# sdmapper.net
KiCad netlist of a schematic drawn in EAGLE
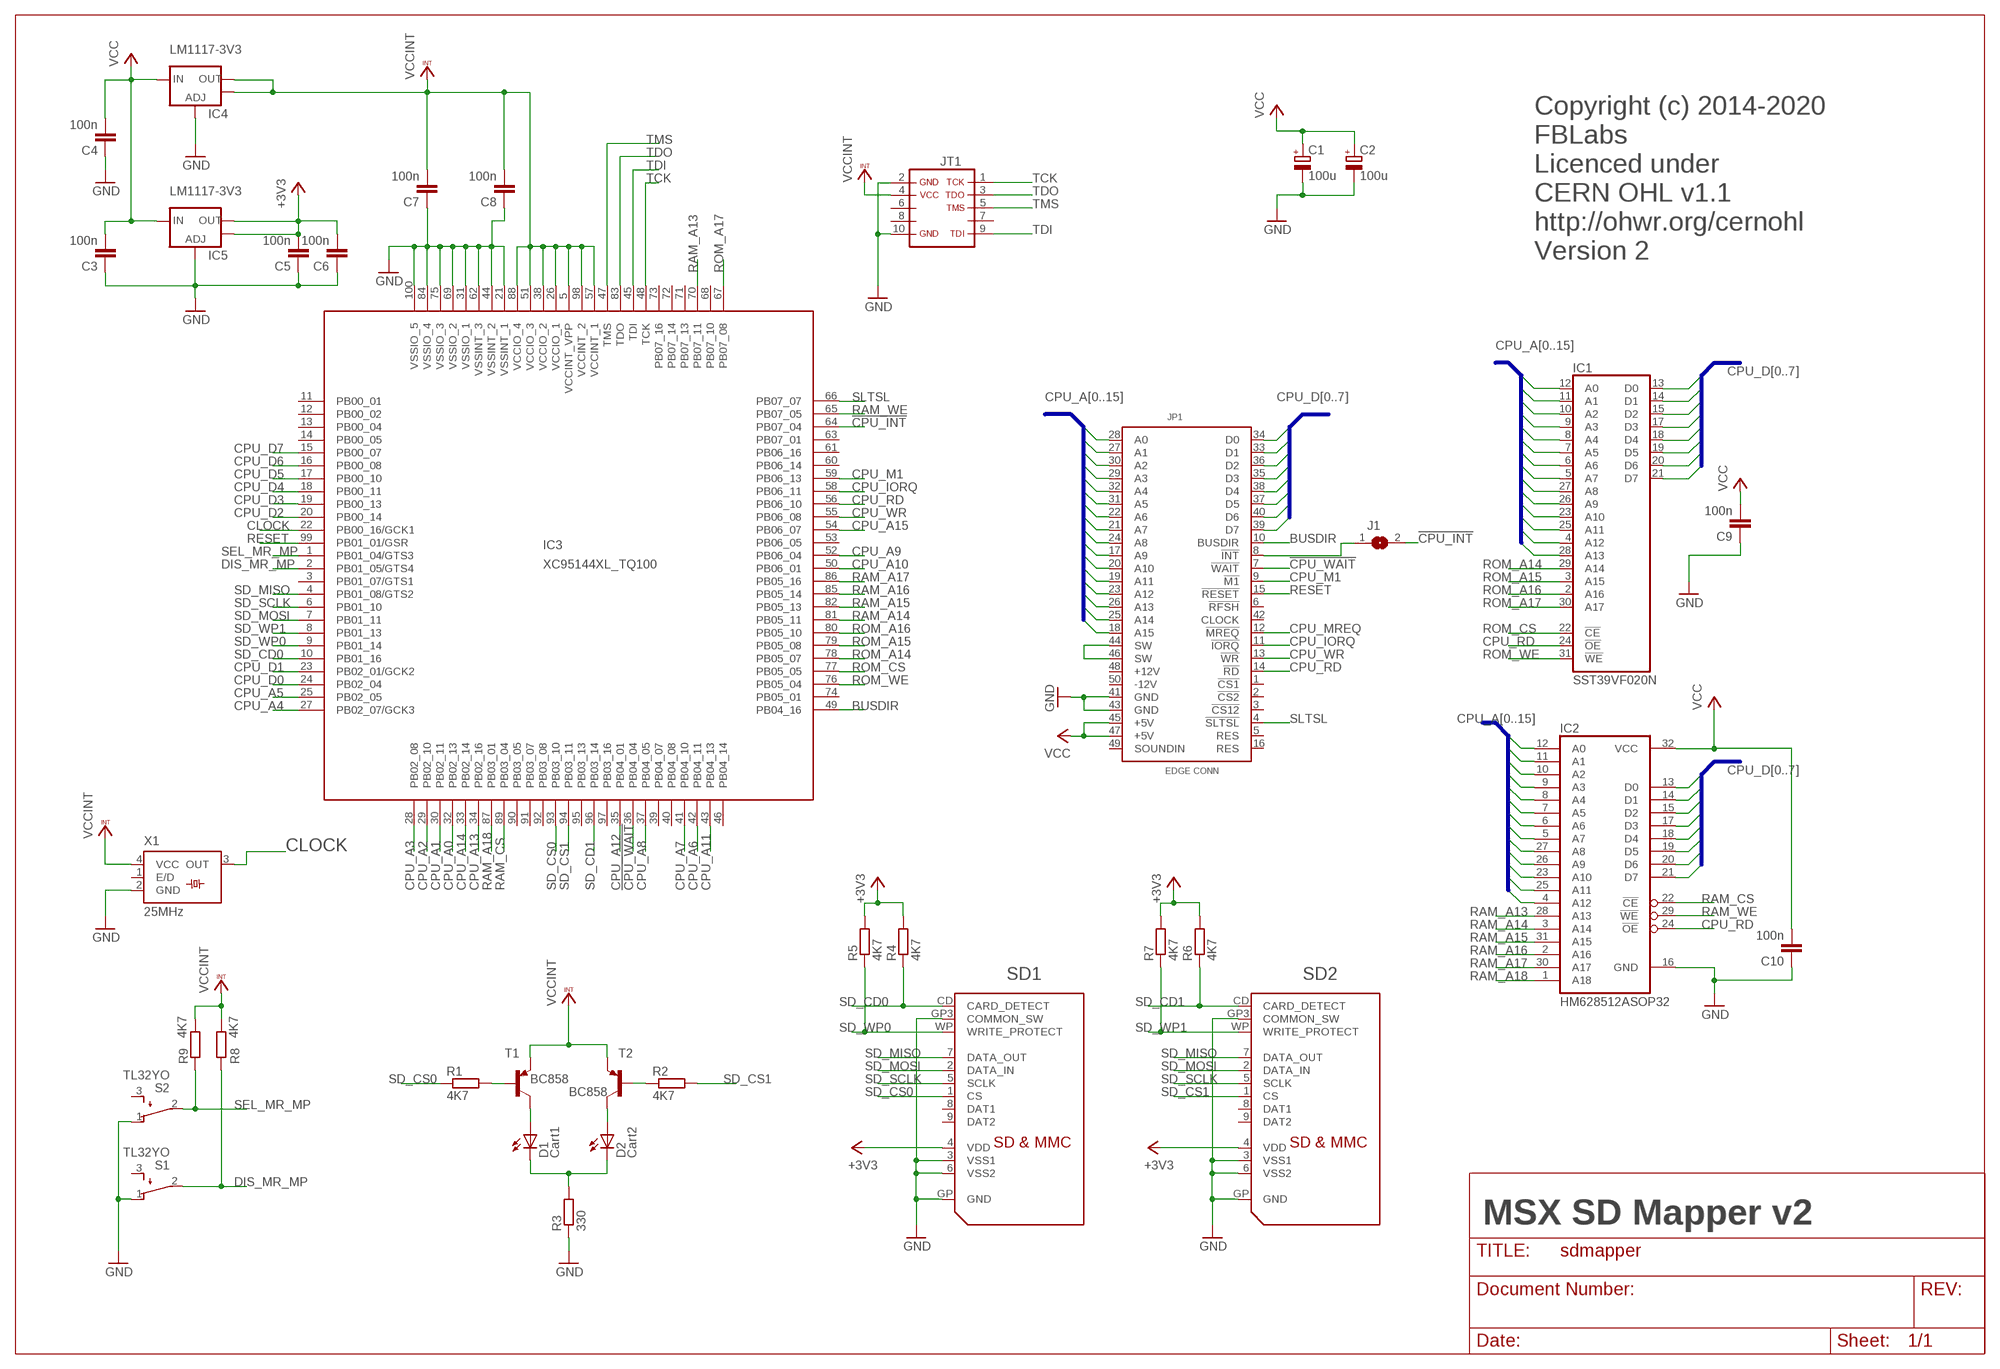
[diagram p0: schematic, sheet 1]

(export (version "E")
  (design (tool "Eeschema 10.0.6"))
  (components
    (comp (ref "C1")
      (value "100u")
      (footprint "eagle-import:E3,5-6")
      (libsource (lib "eagle-import") (part "CPOL-EUE3,5-6"))
    )
    (comp (ref "C2")
      (value "100u")
      (footprint "eagle-import:PANASONIC_C")
      (libsource (lib "eagle-import") (part "CPOL-EUC"))
    )
    (comp (ref "C3")
      (value "100n")
      (footprint "eagle-import:C0805")
      (libsource (lib "eagle-import") (part "C-EUC0805"))
    )
    (comp (ref "C4")
      (value "100n")
      (footprint "eagle-import:C0805")
      (libsource (lib "eagle-import") (part "C-EUC0805"))
    )
    (comp (ref "C5")
      (value "100n")
      (footprint "eagle-import:C0805")
      (libsource (lib "eagle-import") (part "C-EUC0805"))
    )
    (comp (ref "C6")
      (value "100n")
      (footprint "eagle-import:C0805")
      (libsource (lib "eagle-import") (part "C-EUC0805"))
    )
    (comp (ref "C7")
      (value "100n")
      (footprint "eagle-import:C0805")
      (libsource (lib "eagle-import") (part "C-EUC0805"))
    )
    (comp (ref "C8")
      (value "100n")
      (footprint "eagle-import:C0805")
      (libsource (lib "eagle-import") (part "C-EUC0805"))
    )
    (comp (ref "C9")
      (value "100n")
      (footprint "eagle-import:C0805")
      (libsource (lib "eagle-import") (part "C-EUC0805"))
    )
    (comp (ref "C10")
      (value "100n")
      (footprint "eagle-import:C0805")
      (libsource (lib "eagle-import") (part "C-EUC0805"))
    )
    (comp (ref "D1")
      (value "Cart1")
      (footprint "eagle-import:LED3MM")
      (libsource (lib "eagle-import") (part "LED3MM"))
    )
    (comp (ref "D2")
      (value "Cart2")
      (footprint "eagle-import:LED3MM")
      (libsource (lib "eagle-import") (part "LED3MM"))
    )
    (comp (ref "IC1")
      (value "SST39VF020N")
      (footprint "eagle-import:PLCC32R")
      (libsource (lib "eagle-import") (part "SST39VF020N"))
    )
    (comp (ref "IC2")
      (value "HM628512ASOP32")
      (footprint "eagle-import:SOP32")
      (libsource (lib "eagle-import") (part "HM628512ASOP32"))
    )
    (comp (ref "IC3")
      (value "XC95144XL_TQ100")
      (footprint "eagle-import:XC-TQ100")
      (libsource (lib "eagle-import") (part "XC95144XL_TQ100"))
    )
    (comp (ref "IC4")
      (value "LM1117-3V3")
      (footprint "eagle-import:SOT223")
      (libsource (lib "eagle-import") (part "V_REG_LM1117SOT223"))
    )
    (comp (ref "IC5")
      (value "LM1117-3V3")
      (footprint "eagle-import:SOT223")
      (libsource (lib "eagle-import") (part "V_REG_LM1117SOT223"))
    )
    (comp (ref "J1")
      (value "SJ4")
      (footprint "eagle-import:SJ20")
      (libsource (lib "eagle-import") (part "SJ4"))
    )
    (comp (ref "JP1")
      (value "MSXCART1")
      (footprint "eagle-import:MSXCART")
      (libsource (lib "eagle-import") (part "MSXCART1"))
    )
    (comp (ref "JT1")
      (value "JTAG1B")
      (footprint "eagle-import:SMD5X2")
      (libsource (lib "eagle-import") (part "JTAG1B"))
    )
    (comp (ref "R1")
      (value "4K7")
      (footprint "eagle-import:R0805")
      (libsource (lib "eagle-import") (part "R-EU_R0805"))
    )
    (comp (ref "R2")
      (value "4K7")
      (footprint "eagle-import:R0805")
      (libsource (lib "eagle-import") (part "R-EU_R0805"))
    )
    (comp (ref "R3")
      (value "330")
      (footprint "eagle-import:R0805")
      (libsource (lib "eagle-import") (part "R-EU_R0805"))
    )
    (comp (ref "R4")
      (value "4K7")
      (footprint "eagle-import:R0805")
      (libsource (lib "eagle-import") (part "R-EU_R0805"))
    )
    (comp (ref "R5")
      (value "4K7")
      (footprint "eagle-import:R0805")
      (libsource (lib "eagle-import") (part "R-EU_R0805"))
    )
    (comp (ref "R6")
      (value "4K7")
      (footprint "eagle-import:R0805")
      (libsource (lib "eagle-import") (part "R-EU_R0805"))
    )
    (comp (ref "R7")
      (value "4K7")
      (footprint "eagle-import:R0805")
      (libsource (lib "eagle-import") (part "R-EU_R0805"))
    )
    (comp (ref "R8")
      (value "4K7")
      (footprint "eagle-import:R0805")
      (libsource (lib "eagle-import") (part "R-EU_R0805"))
    )
    (comp (ref "R9")
      (value "4K7")
      (footprint "eagle-import:R0805")
      (libsource (lib "eagle-import") (part "R-EU_R0805"))
    )
    (comp (ref "S1")
      (value "TL32YO")
      (footprint "eagle-import:TL3XYO")
      (libsource (lib "eagle-import") (part "TL32YO"))
    )
    (comp (ref "S2")
      (value "TL32YO")
      (footprint "eagle-import:TL3XYO")
      (libsource (lib "eagle-import") (part "TL32YO"))
    )
    (comp (ref "SD1")
      (value "SDMMC06132")
      (footprint "eagle-import:06132")
      (libsource (lib "eagle-import") (part "SDMMC06132"))
    )
    (comp (ref "SD2")
      (value "SDMMC06132")
      (footprint "eagle-import:06132")
      (libsource (lib "eagle-import") (part "SDMMC06132"))
    )
    (comp (ref "T1")
      (value "BC858")
      (footprint "eagle-import:SOT23-BEC")
      (libsource (lib "eagle-import") (part "-PNP-SOT23-BECBC858A"))
    )
    (comp (ref "T2")
      (value "BC858")
      (footprint "eagle-import:SOT23-BEC")
      (libsource (lib "eagle-import") (part "-PNP-SOT23-BECBC858A"))
    )
    (comp (ref "X1")
      (value "25MHz")
      (footprint "eagle-import:SM77H")
      (libsource (lib "eagle-import") (part "SM77H"))
    )
  )
  (nets
    (net (code "1") (name "+3V3") (class "Default")
      (node (ref "C5") (pin "2") (pinfunction "2_2") (pintype "passive"))
      (node (ref "C6") (pin "2") (pinfunction "2_2") (pintype "passive"))
      (node (ref "IC5") (pin "2") (pinfunction "OUT_2") (pintype "output"))
      (node (ref "IC5") (pin "4") (pinfunction "OUT_4") (pintype "output"))
      (node (ref "R4") (pin "2") (pinfunction "2_2") (pintype "passive"))
      (node (ref "R5") (pin "2") (pinfunction "2_2") (pintype "passive"))
      (node (ref "R6") (pin "2") (pinfunction "2_2") (pintype "passive"))
      (node (ref "R7") (pin "2") (pinfunction "2_2") (pintype "passive"))
      (node (ref "SD1") (pin "4") (pinfunction "VDD_4") (pintype "power_in"))
      (node (ref "SD2") (pin "4") (pinfunction "VDD_4") (pintype "power_in"))
    )
    (net (code "2") (name "/+12V") (class "Default")
      (node (ref "JP1") (pin "48") (pinfunction "+12V_48") (pintype "power_in"))
    )
    (net (code "3") (name "/-12V") (class "Default")
      (node (ref "JP1") (pin "50") (pinfunction "-12V_50") (pintype "power_in"))
    )
    (net (code "4") (name "/BUSDIR") (class "Default")
      (node (ref "IC3") (pin "49") (pinfunction "PB04_16_49") (pintype "bidirectional"))
      (node (ref "JP1") (pin "10") (pinfunction "BUSDIR_10") (pintype "input"))
    )
    (net (code "5") (name "/CLOCK") (class "Default")
      (node (ref "IC3") (pin "22") (pinfunction "PB00_16/GCK1_22") (pintype "bidirectional"))
      (node (ref "X1") (pin "3") (pinfunction "OUT_3") (pintype "output"))
    )
    (net (code "6") (name "/CPU_A0") (class "Default")
      (node (ref "IC1") (pin "12") (pinfunction "A0_12") (pintype "input"))
      (node (ref "IC2") (pin "12") (pinfunction "A0_12") (pintype "input"))
      (node (ref "IC3") (pin "32") (pinfunction "PB02_13_32") (pintype "bidirectional"))
      (node (ref "JP1") (pin "28") (pinfunction "A0_28") (pintype "output"))
    )
    (net (code "7") (name "/CPU_A1") (class "Default")
      (node (ref "IC1") (pin "11") (pinfunction "A1_11") (pintype "input"))
      (node (ref "IC2") (pin "11") (pinfunction "A1_11") (pintype "input"))
      (node (ref "IC3") (pin "30") (pinfunction "PB02_11_30") (pintype "bidirectional"))
      (node (ref "JP1") (pin "27") (pinfunction "A1_27") (pintype "output"))
    )
    (net (code "8") (name "/CPU_A2") (class "Default")
      (node (ref "IC1") (pin "10") (pinfunction "A2_10") (pintype "input"))
      (node (ref "IC2") (pin "10") (pinfunction "A2_10") (pintype "input"))
      (node (ref "IC3") (pin "29") (pinfunction "PB02_10_29") (pintype "bidirectional"))
      (node (ref "JP1") (pin "30") (pinfunction "A2_30") (pintype "output"))
    )
    (net (code "9") (name "/CPU_A3") (class "Default")
      (node (ref "IC1") (pin "9") (pinfunction "A3_9") (pintype "input"))
      (node (ref "IC2") (pin "9") (pinfunction "A3_9") (pintype "input"))
      (node (ref "IC3") (pin "28") (pinfunction "PB02_08_28") (pintype "bidirectional"))
      (node (ref "JP1") (pin "29") (pinfunction "A3_29") (pintype "output"))
    )
    (net (code "10") (name "/CPU_A4") (class "Default")
      (node (ref "IC1") (pin "8") (pinfunction "A4_8") (pintype "input"))
      (node (ref "IC2") (pin "8") (pinfunction "A4_8") (pintype "input"))
      (node (ref "IC3") (pin "27") (pinfunction "PB02_07/GCK3_27") (pintype "bidirectional"))
      (node (ref "JP1") (pin "32") (pinfunction "A4_32") (pintype "output"))
    )
    (net (code "11") (name "/CPU_A5") (class "Default")
      (node (ref "IC1") (pin "7") (pinfunction "A5_7") (pintype "input"))
      (node (ref "IC2") (pin "7") (pinfunction "A5_7") (pintype "input"))
      (node (ref "IC3") (pin "25") (pinfunction "PB02_05_25") (pintype "bidirectional"))
      (node (ref "JP1") (pin "31") (pinfunction "A5_31") (pintype "output"))
    )
    (net (code "12") (name "/CPU_A6") (class "Default")
      (node (ref "IC1") (pin "6") (pinfunction "A6_6") (pintype "input"))
      (node (ref "IC2") (pin "6") (pinfunction "A6_6") (pintype "input"))
      (node (ref "IC3") (pin "42") (pinfunction "PB04_11_42") (pintype "bidirectional"))
      (node (ref "JP1") (pin "22") (pinfunction "A6_22") (pintype "output"))
    )
    (net (code "13") (name "/CPU_A7") (class "Default")
      (node (ref "IC1") (pin "5") (pinfunction "A7_5") (pintype "input"))
      (node (ref "IC2") (pin "5") (pinfunction "A7_5") (pintype "input"))
      (node (ref "IC3") (pin "41") (pinfunction "PB04_10_41") (pintype "bidirectional"))
      (node (ref "JP1") (pin "21") (pinfunction "A7_21") (pintype "output"))
    )
    (net (code "14") (name "/CPU_A8") (class "Default")
      (node (ref "IC1") (pin "27") (pinfunction "A8_27") (pintype "input"))
      (node (ref "IC2") (pin "27") (pinfunction "A8_27") (pintype "input"))
      (node (ref "IC3") (pin "37") (pinfunction "PB04_05_37") (pintype "bidirectional"))
      (node (ref "JP1") (pin "24") (pinfunction "A8_24") (pintype "output"))
    )
    (net (code "15") (name "/CPU_A9") (class "Default")
      (node (ref "IC1") (pin "26") (pinfunction "A9_26") (pintype "input"))
      (node (ref "IC2") (pin "26") (pinfunction "A9_26") (pintype "input"))
      (node (ref "IC3") (pin "52") (pinfunction "PB06_04_52") (pintype "bidirectional"))
      (node (ref "JP1") (pin "17") (pinfunction "A9_17") (pintype "output"))
    )
    (net (code "16") (name "/CPU_A10") (class "Default")
      (node (ref "IC1") (pin "23") (pinfunction "A10_23") (pintype "input"))
      (node (ref "IC2") (pin "23") (pinfunction "A10_23") (pintype "input"))
      (node (ref "IC3") (pin "50") (pinfunction "PB06_01_50") (pintype "bidirectional"))
      (node (ref "JP1") (pin "20") (pinfunction "A10_20") (pintype "output"))
    )
    (net (code "17") (name "/CPU_A11") (class "Default")
      (node (ref "IC1") (pin "25") (pinfunction "A11_25") (pintype "input"))
      (node (ref "IC2") (pin "25") (pinfunction "A11_25") (pintype "input"))
      (node (ref "IC3") (pin "43") (pinfunction "PB04_13_43") (pintype "bidirectional"))
      (node (ref "JP1") (pin "19") (pinfunction "A11_19") (pintype "output"))
    )
    (net (code "18") (name "/CPU_A12") (class "Default")
      (node (ref "IC1") (pin "4") (pinfunction "A12_4") (pintype "input"))
      (node (ref "IC2") (pin "4") (pinfunction "A12_4") (pintype "input"))
      (node (ref "IC3") (pin "35") (pinfunction "PB04_01_35") (pintype "bidirectional"))
      (node (ref "JP1") (pin "23") (pinfunction "A12_23") (pintype "output"))
    )
    (net (code "19") (name "/CPU_A13") (class "Default")
      (node (ref "IC1") (pin "28") (pinfunction "A13_28") (pintype "input"))
      (node (ref "IC3") (pin "34") (pinfunction "PB02_16_34") (pintype "bidirectional"))
      (node (ref "JP1") (pin "26") (pinfunction "A13_26") (pintype "output"))
    )
    (net (code "20") (name "/CPU_A14") (class "Default")
      (node (ref "IC3") (pin "33") (pinfunction "PB02_14_33") (pintype "bidirectional"))
      (node (ref "JP1") (pin "25") (pinfunction "A14_25") (pintype "output"))
    )
    (net (code "21") (name "/CPU_A15") (class "Default")
      (node (ref "IC3") (pin "54") (pinfunction "PB06_07_54") (pintype "bidirectional"))
      (node (ref "JP1") (pin "18") (pinfunction "A15_18") (pintype "output"))
    )
    (net (code "23") (name "/CPU_D0") (class "Default")
      (node (ref "IC1") (pin "13") (pinfunction "D0_13") (pintype "bidirectional"))
      (node (ref "IC2") (pin "13") (pinfunction "D0_13") (pintype "bidirectional"))
      (node (ref "IC3") (pin "24") (pinfunction "PB02_04_24") (pintype "bidirectional"))
      (node (ref "JP1") (pin "34") (pinfunction "D0_34") (pintype "bidirectional"))
    )
    (net (code "24") (name "/CPU_D1") (class "Default")
      (node (ref "IC1") (pin "14") (pinfunction "D1_14") (pintype "bidirectional"))
      (node (ref "IC2") (pin "14") (pinfunction "D1_14") (pintype "bidirectional"))
      (node (ref "IC3") (pin "23") (pinfunction "PB02_01/GCK2_23") (pintype "bidirectional"))
      (node (ref "JP1") (pin "33") (pinfunction "D1_33") (pintype "bidirectional"))
    )
    (net (code "25") (name "/CPU_D2") (class "Default")
      (node (ref "IC1") (pin "15") (pinfunction "D2_15") (pintype "bidirectional"))
      (node (ref "IC2") (pin "15") (pinfunction "D2_15") (pintype "bidirectional"))
      (node (ref "IC3") (pin "20") (pinfunction "PB00_14_20") (pintype "bidirectional"))
      (node (ref "JP1") (pin "36") (pinfunction "D2_36") (pintype "bidirectional"))
    )
    (net (code "26") (name "/CPU_D3") (class "Default")
      (node (ref "IC1") (pin "17") (pinfunction "D3_17") (pintype "bidirectional"))
      (node (ref "IC2") (pin "17") (pinfunction "D3_17") (pintype "bidirectional"))
      (node (ref "IC3") (pin "19") (pinfunction "PB00_13_19") (pintype "bidirectional"))
      (node (ref "JP1") (pin "35") (pinfunction "D3_35") (pintype "bidirectional"))
    )
    (net (code "27") (name "/CPU_D4") (class "Default")
      (node (ref "IC1") (pin "18") (pinfunction "D4_18") (pintype "bidirectional"))
      (node (ref "IC2") (pin "18") (pinfunction "D4_18") (pintype "bidirectional"))
      (node (ref "IC3") (pin "18") (pinfunction "PB00_11_18") (pintype "bidirectional"))
      (node (ref "JP1") (pin "38") (pinfunction "D4_38") (pintype "bidirectional"))
    )
    (net (code "28") (name "/CPU_D5") (class "Default")
      (node (ref "IC1") (pin "19") (pinfunction "D5_19") (pintype "bidirectional"))
      (node (ref "IC2") (pin "19") (pinfunction "D5_19") (pintype "bidirectional"))
      (node (ref "IC3") (pin "17") (pinfunction "PB00_10_17") (pintype "bidirectional"))
      (node (ref "JP1") (pin "37") (pinfunction "D5_37") (pintype "bidirectional"))
    )
    (net (code "29") (name "/CPU_D6") (class "Default")
      (node (ref "IC1") (pin "20") (pinfunction "D6_20") (pintype "bidirectional"))
      (node (ref "IC2") (pin "20") (pinfunction "D6_20") (pintype "bidirectional"))
      (node (ref "IC3") (pin "16") (pinfunction "PB00_08_16") (pintype "bidirectional"))
      (node (ref "JP1") (pin "40") (pinfunction "D6_40") (pintype "bidirectional"))
    )
    (net (code "30") (name "/CPU_D7") (class "Default")
      (node (ref "IC1") (pin "21") (pinfunction "D7_21") (pintype "bidirectional"))
      (node (ref "IC2") (pin "21") (pinfunction "D7_21") (pintype "bidirectional"))
      (node (ref "IC3") (pin "15") (pinfunction "PB00_07_15") (pintype "bidirectional"))
      (node (ref "JP1") (pin "39") (pinfunction "D7_39") (pintype "bidirectional"))
    )
    (net (code "32") (name "/CPU_IORQ") (class "Default")
      (node (ref "IC3") (pin "58") (pinfunction "PB06_11_58") (pintype "bidirectional"))
      (node (ref "JP1") (pin "11") (pinfunction "~{IORQ}_11") (pintype "output"))
    )
    (net (code "33") (name "/CPU_M1") (class "Default")
      (node (ref "IC3") (pin "59") (pinfunction "PB06_13_59") (pintype "bidirectional"))
      (node (ref "JP1") (pin "9") (pinfunction "~{M1}_9") (pintype "output"))
    )
    (net (code "34") (name "/CPU_MREQ") (class "Default")
      (node (ref "JP1") (pin "12") (pinfunction "~{MREQ}_12") (pintype "output"))
    )
    (net (code "35") (name "/CPU_RD") (class "Default")
      (node (ref "IC1") (pin "24") (pinfunction "~{OE}_24") (pintype "input"))
      (node (ref "IC2") (pin "24") (pinfunction "~{OE}_24") (pintype "input"))
      (node (ref "IC3") (pin "56") (pinfunction "PB06_10_56") (pintype "bidirectional"))
      (node (ref "JP1") (pin "14") (pinfunction "~{RD}_14") (pintype "output"))
    )
    (net (code "36") (name "/CPU_WR") (class "Default")
      (node (ref "IC3") (pin "55") (pinfunction "PB06_08_55") (pintype "bidirectional"))
      (node (ref "JP1") (pin "13") (pinfunction "~{WR}_13") (pintype "output"))
    )
    (net (code "37") (name "/DIS_MR_MP") (class "Default")
      (node (ref "IC3") (pin "2") (pinfunction "PB01_05/GTS4_2") (pintype "bidirectional"))
      (node (ref "R8") (pin "1") (pinfunction "1_1") (pintype "passive"))
      (node (ref "S1") (pin "2") (pinfunction "P_2") (pintype "passive"))
    )
    (net (code "38") (name "/RAM_A13") (class "Default")
      (node (ref "IC2") (pin "28") (pinfunction "A13_28") (pintype "input"))
      (node (ref "IC3") (pin "70") (pinfunction "PB07_11_70") (pintype "bidirectional"))
    )
    (net (code "39") (name "/RAM_A14") (class "Default")
      (node (ref "IC2") (pin "3") (pinfunction "A14_3") (pintype "input"))
      (node (ref "IC3") (pin "81") (pinfunction "PB05_11_81") (pintype "bidirectional"))
    )
    (net (code "40") (name "/RAM_A15") (class "Default")
      (node (ref "IC2") (pin "31") (pinfunction "A15_31") (pintype "input"))
      (node (ref "IC3") (pin "82") (pinfunction "PB05_13_82") (pintype "bidirectional"))
    )
    (net (code "41") (name "/RAM_A16") (class "Default")
      (node (ref "IC2") (pin "2") (pinfunction "A16_2") (pintype "input"))
      (node (ref "IC3") (pin "85") (pinfunction "PB05_14_85") (pintype "bidirectional"))
    )
    (net (code "42") (name "/RAM_A17") (class "Default")
      (node (ref "IC2") (pin "30") (pinfunction "A17_30") (pintype "input"))
      (node (ref "IC3") (pin "86") (pinfunction "PB05_16_86") (pintype "bidirectional"))
    )
    (net (code "43") (name "/RAM_A18") (class "Default")
      (node (ref "IC2") (pin "1") (pinfunction "A18_1") (pintype "input"))
      (node (ref "IC3") (pin "87") (pinfunction "PB03_01_87") (pintype "bidirectional"))
    )
    (net (code "44") (name "/RAM_CS") (class "Default")
      (node (ref "IC2") (pin "22") (pinfunction "~{CE}_22") (pintype "input"))
      (node (ref "IC3") (pin "89") (pinfunction "PB03_04_89") (pintype "bidirectional"))
    )
    (net (code "45") (name "/RAM_WE") (class "Default")
      (node (ref "IC2") (pin "29") (pinfunction "~{WE}_29") (pintype "input"))
      (node (ref "IC3") (pin "65") (pinfunction "PB07_05_65") (pintype "bidirectional"))
    )
    (net (code "46") (name "/RESET") (class "Default")
      (node (ref "IC3") (pin "99") (pinfunction "PB01_01/GSR_99") (pintype "bidirectional"))
      (node (ref "JP1") (pin "15") (pinfunction "~{RESET}_15") (pintype "output"))
    )
    (net (code "47") (name "/ROM_A14") (class "Default")
      (node (ref "IC1") (pin "29") (pinfunction "A14_29") (pintype "input"))
      (node (ref "IC3") (pin "78") (pinfunction "PB05_07_78") (pintype "bidirectional"))
    )
    (net (code "48") (name "/ROM_A15") (class "Default")
      (node (ref "IC1") (pin "3") (pinfunction "A15_3") (pintype "input"))
      (node (ref "IC3") (pin "79") (pinfunction "PB05_08_79") (pintype "bidirectional"))
    )
    (net (code "49") (name "/ROM_A16") (class "Default")
      (node (ref "IC1") (pin "2") (pinfunction "A16_2") (pintype "input"))
      (node (ref "IC3") (pin "80") (pinfunction "PB05_10_80") (pintype "bidirectional"))
    )
    (net (code "50") (name "/ROM_A17") (class "Default")
      (node (ref "IC1") (pin "30") (pinfunction "A17_30") (pintype "input"))
      (node (ref "IC3") (pin "67") (pinfunction "PB07_08_67") (pintype "bidirectional"))
    )
    (net (code "51") (name "/ROM_CS") (class "Default")
      (node (ref "IC1") (pin "22") (pinfunction "~{CE}_22") (pintype "input"))
      (node (ref "IC3") (pin "77") (pinfunction "PB05_05_77") (pintype "bidirectional"))
    )
    (net (code "52") (name "/ROM_WE") (class "Default")
      (node (ref "IC1") (pin "31") (pinfunction "~{WE}_31") (pintype "input"))
      (node (ref "IC3") (pin "76") (pinfunction "PB05_04_76") (pintype "bidirectional"))
    )
    (net (code "53") (name "/SD_CD0") (class "Default")
      (node (ref "IC3") (pin "10") (pinfunction "PB01_16_10") (pintype "bidirectional"))
      (node (ref "R4") (pin "1") (pinfunction "1_1") (pintype "passive"))
      (node (ref "SD1") (pin "CD") (pinfunction "CARD_DETECT_CD") (pintype "passive"))
    )
    (net (code "54") (name "/SD_CD1") (class "Default")
      (node (ref "IC3") (pin "96") (pinfunction "PB03_14_96") (pintype "bidirectional"))
      (node (ref "R6") (pin "1") (pinfunction "1_1") (pintype "passive"))
      (node (ref "SD2") (pin "CD") (pinfunction "CARD_DETECT_CD") (pintype "passive"))
    )
    (net (code "55") (name "/SD_CS0") (class "Default")
      (node (ref "IC3") (pin "93") (pinfunction "PB03_10_93") (pintype "bidirectional"))
      (node (ref "R1") (pin "1") (pinfunction "1_1") (pintype "passive"))
      (node (ref "SD1") (pin "1") (pinfunction "CS_1") (pintype "input"))
    )
    (net (code "56") (name "/SD_CS1") (class "Default")
      (node (ref "IC3") (pin "94") (pinfunction "PB03_11_94") (pintype "bidirectional"))
      (node (ref "R2") (pin "2") (pinfunction "2_2") (pintype "passive"))
      (node (ref "SD2") (pin "1") (pinfunction "CS_1") (pintype "input"))
    )
    (net (code "57") (name "/SD_MISO") (class "Default")
      (node (ref "IC3") (pin "4") (pinfunction "PB01_08/GTS2_4") (pintype "bidirectional"))
      (node (ref "SD1") (pin "7") (pinfunction "DATA_OUT_7") (pintype "output"))
      (node (ref "SD2") (pin "7") (pinfunction "DATA_OUT_7") (pintype "output"))
    )
    (net (code "58") (name "/SD_MOSI") (class "Default")
      (node (ref "IC3") (pin "7") (pinfunction "PB01_11_7") (pintype "bidirectional"))
      (node (ref "SD1") (pin "2") (pinfunction "DATA_IN_2") (pintype "input"))
      (node (ref "SD2") (pin "2") (pinfunction "DATA_IN_2") (pintype "input"))
    )
    (net (code "59") (name "/SD_SCLK") (class "Default")
      (node (ref "IC3") (pin "6") (pinfunction "PB01_10_6") (pintype "bidirectional"))
      (node (ref "SD1") (pin "5") (pinfunction "SCLK_5") (pintype "input"))
      (node (ref "SD2") (pin "5") (pinfunction "SCLK_5") (pintype "input"))
    )
    (net (code "60") (name "/SD_WP0") (class "Default")
      (node (ref "IC3") (pin "9") (pinfunction "PB01_14_9") (pintype "bidirectional"))
      (node (ref "R5") (pin "1") (pinfunction "1_1") (pintype "passive"))
      (node (ref "SD1") (pin "WP") (pinfunction "WRITE_PROTECT_WP") (pintype "passive"))
    )
    (net (code "61") (name "/SD_WP1") (class "Default")
      (node (ref "IC3") (pin "8") (pinfunction "PB01_13_8") (pintype "bidirectional"))
      (node (ref "R7") (pin "1") (pinfunction "1_1") (pintype "passive"))
      (node (ref "SD2") (pin "WP") (pinfunction "WRITE_PROTECT_WP") (pintype "passive"))
    )
    (net (code "62") (name "/SEL_MR_MP") (class "Default")
      (node (ref "IC3") (pin "1") (pinfunction "PB01_04/GTS3_1") (pintype "bidirectional"))
      (node (ref "R9") (pin "1") (pinfunction "1_1") (pintype "passive"))
      (node (ref "S2") (pin "2") (pinfunction "P_2") (pintype "passive"))
    )
    (net (code "63") (name "/SLTSL") (class "Default")
      (node (ref "IC3") (pin "66") (pinfunction "PB07_07_66") (pintype "bidirectional"))
      (node (ref "JP1") (pin "4") (pinfunction "~{SLTSL}_4") (pintype "output"))
    )
    (net (code "64") (name "/TCK") (class "Default")
      (node (ref "IC3") (pin "48") (pinfunction "TCK_48") (pintype "input"))
      (node (ref "JT1") (pin "1") (pinfunction "1_1") (pintype "passive"))
    )
    (net (code "65") (name "/TDI") (class "Default")
      (node (ref "IC3") (pin "45") (pinfunction "TDI_45") (pintype "input"))
      (node (ref "JT1") (pin "9") (pinfunction "9_9") (pintype "passive"))
    )
    (net (code "66") (name "/TDO") (class "Default")
      (node (ref "IC3") (pin "83") (pinfunction "TDO_83") (pintype "output"))
      (node (ref "JT1") (pin "3") (pinfunction "3_3") (pintype "passive"))
    )
    (net (code "67") (name "/TMS") (class "Default")
      (node (ref "IC3") (pin "47") (pinfunction "TMS_47") (pintype "input"))
      (node (ref "JT1") (pin "5") (pinfunction "5_5") (pintype "passive"))
    )
    (net (code "68") (name "/~{CPU_INT}") (class "Default")
      (node (ref "IC3") (pin "64") (pinfunction "PB07_04_64") (pintype "bidirectional"))
      (node (ref "J1") (pin "2") (pinfunction "2_2") (pintype "passive"))
    )
    (net (code "69") (name "/~{CPU_WAIT}") (class "Default")
      (node (ref "IC3") (pin "36") (pinfunction "PB04_04_36") (pintype "bidirectional"))
      (node (ref "JP1") (pin "7") (pinfunction "~{WAIT}_7") (pintype "open_collector"))
    )
    (net (code "70") (name "GND") (class "Default")
      (node (ref "C1") (pin "-") (pinfunction "-_-") (pintype "passive"))
      (node (ref "C10") (pin "1") (pinfunction "1_1") (pintype "passive"))
      (node (ref "C2") (pin "-") (pinfunction "-_-") (pintype "passive"))
      (node (ref "C3") (pin "1") (pinfunction "1_1") (pintype "passive"))
      (node (ref "C4") (pin "1") (pinfunction "1_1") (pintype "passive"))
      (node (ref "C5") (pin "1") (pinfunction "1_1") (pintype "passive"))
      (node (ref "C6") (pin "1") (pinfunction "1_1") (pintype "passive"))
      (node (ref "C7") (pin "1") (pinfunction "1_1") (pintype "passive"))
      (node (ref "C8") (pin "1") (pinfunction "1_1") (pintype "passive"))
      (node (ref "C9") (pin "1") (pinfunction "1_1") (pintype "passive"))
      (node (ref "IC2") (pin "16") (pinfunction "GND_16") (pintype "power_in"))
      (node (ref "IC3") (pin "100") (pinfunction "VSSIO_5_100") (pintype "passive"))
      (node (ref "IC3") (pin "21") (pinfunction "VSSINT_1_21") (pintype "passive"))
      (node (ref "IC3") (pin "31") (pinfunction "VSSIO_1_31") (pintype "passive"))
      (node (ref "IC3") (pin "44") (pinfunction "VSSINT_2_44") (pintype "passive"))
      (node (ref "IC3") (pin "62") (pinfunction "VSSINT_3_62") (pintype "passive"))
      (node (ref "IC3") (pin "69") (pinfunction "VSSIO_2_69") (pintype "passive"))
      (node (ref "IC3") (pin "75") (pinfunction "VSSIO_3_75") (pintype "passive"))
      (node (ref "IC3") (pin "84") (pinfunction "VSSIO_4_84") (pintype "passive"))
      (node (ref "IC4") (pin "1") (pinfunction "ADJ_1") (pintype "input"))
      (node (ref "IC5") (pin "1") (pinfunction "ADJ_1") (pintype "input"))
      (node (ref "JP1") (pin "41") (pinfunction "GND_41") (pintype "power_in"))
      (node (ref "JP1") (pin "43") (pinfunction "GND_43") (pintype "power_in"))
      (node (ref "JT1") (pin "10") (pinfunction "10_10") (pintype "passive"))
      (node (ref "JT1") (pin "2") (pinfunction "2_2") (pintype "passive"))
      (node (ref "R3") (pin "1") (pinfunction "1_1") (pintype "passive"))
      (node (ref "S1") (pin "1") (pinfunction "O_1") (pintype "passive"))
      (node (ref "S2") (pin "1") (pinfunction "O_1") (pintype "passive"))
      (node (ref "SD1") (pin "3") (pinfunction "VSS1_3") (pintype "power_in"))
      (node (ref "SD1") (pin "6") (pinfunction "VSS2_6") (pintype "power_in"))
      (node (ref "SD1") (pin "GP") (pinfunction "GND_GP") (pintype "power_in"))
      (node (ref "SD1") (pin "GP3") (pinfunction "COMMON_SW_GP3") (pintype "passive"))
      (node (ref "SD2") (pin "3") (pinfunction "VSS1_3") (pintype "power_in"))
      (node (ref "SD2") (pin "6") (pinfunction "VSS2_6") (pintype "power_in"))
      (node (ref "SD2") (pin "GP") (pinfunction "GND_GP") (pintype "power_in"))
      (node (ref "SD2") (pin "GP3") (pinfunction "COMMON_SW_GP3") (pintype "passive"))
      (node (ref "X1") (pin "2") (pinfunction "GND_2") (pintype "power_in"))
    )
    (net (code "71") (name "Net-(D1-C)") (class "Default")
      (node (ref "D1") (pin "K") (pinfunction "C_K") (pintype "passive"))
      (node (ref "D2") (pin "K") (pinfunction "C_K") (pintype "passive"))
      (node (ref "R3") (pin "2") (pinfunction "2_2") (pintype "passive"))
    )
    (net (code "72") (name "Net-(D1-PadA)") (class "Default")
      (node (ref "D1") (pin "A") (pinfunction "A_A") (pintype "passive"))
      (node (ref "T1") (pin "C") (pinfunction "C_C") (pintype "passive"))
    )
    (net (code "73") (name "Net-(D2-PadA)") (class "Default")
      (node (ref "D2") (pin "A") (pinfunction "A_A") (pintype "passive"))
      (node (ref "T2") (pin "C") (pinfunction "C_C") (pintype "passive"))
    )
    (net (code "74") (name "Net-(JP1-SW-Pad44)") (class "Default")
      (node (ref "JP1") (pin "44") (pinfunction "SW_44") (pintype "passive"))
      (node (ref "JP1") (pin "46") (pinfunction "SW_46") (pintype "passive"))
    )
    (net (code "75") (name "Net-(JP1-~{INT})") (class "Default")
      (node (ref "J1") (pin "1") (pinfunction "1_1") (pintype "passive"))
      (node (ref "JP1") (pin "8") (pinfunction "~{INT}_8") (pintype "open_collector"))
    )
    (net (code "76") (name "Net-(R1-Pad2)") (class "Default")
      (node (ref "R1") (pin "2") (pinfunction "2_2") (pintype "passive"))
      (node (ref "T1") (pin "B") (pinfunction "B_B") (pintype "passive"))
    )
    (net (code "77") (name "Net-(R2-Pad1)") (class "Default")
      (node (ref "R2") (pin "1") (pinfunction "1_1") (pintype "passive"))
      (node (ref "T2") (pin "B") (pinfunction "B_B") (pintype "passive"))
    )
    (net (code "78") (name "VCC") (class "Default")
      (node (ref "C1") (pin "+") (pinfunction "+_+") (pintype "passive"))
      (node (ref "C10") (pin "2") (pinfunction "2_2") (pintype "passive"))
      (node (ref "C2") (pin "+") (pinfunction "+_+") (pintype "passive"))
      (node (ref "C3") (pin "2") (pinfunction "2_2") (pintype "passive"))
      (node (ref "C4") (pin "2") (pinfunction "2_2") (pintype "passive"))
      (node (ref "C9") (pin "2") (pinfunction "2_2") (pintype "passive"))
      (node (ref "IC2") (pin "32") (pinfunction "VCC_32") (pintype "power_in"))
      (node (ref "IC4") (pin "3") (pinfunction "IN_3") (pintype "input"))
      (node (ref "IC5") (pin "3") (pinfunction "IN_3") (pintype "input"))
      (node (ref "JP1") (pin "45") (pinfunction "+5V_45") (pintype "power_in"))
      (node (ref "JP1") (pin "47") (pinfunction "+5V_47") (pintype "power_in"))
    )
    (net (code "79") (name "VCCINT") (class "Default")
      (node (ref "C7") (pin "2") (pinfunction "2_2") (pintype "passive"))
      (node (ref "C8") (pin "2") (pinfunction "2_2") (pintype "passive"))
      (node (ref "IC3") (pin "26") (pinfunction "VCCIO_1_26") (pintype "passive"))
      (node (ref "IC3") (pin "38") (pinfunction "VCCIO_2_38") (pintype "passive"))
      (node (ref "IC3") (pin "5") (pinfunction "VCCINT_VPP_5") (pintype "passive"))
      (node (ref "IC3") (pin "51") (pinfunction "VCCIO_3_51") (pintype "passive"))
      (node (ref "IC3") (pin "57") (pinfunction "VCCINT_1_57") (pintype "passive"))
      (node (ref "IC3") (pin "88") (pinfunction "VCCIO_4_88") (pintype "passive"))
      (node (ref "IC3") (pin "98") (pinfunction "VCCINT_2_98") (pintype "passive"))
      (node (ref "IC4") (pin "2") (pinfunction "OUT_2") (pintype "output"))
      (node (ref "IC4") (pin "4") (pinfunction "OUT_4") (pintype "output"))
      (node (ref "JT1") (pin "4") (pinfunction "4_4") (pintype "passive"))
      (node (ref "R8") (pin "2") (pinfunction "2_2") (pintype "passive"))
      (node (ref "R9") (pin "2") (pinfunction "2_2") (pintype "passive"))
      (node (ref "T1") (pin "E") (pinfunction "E_E") (pintype "passive"))
      (node (ref "T2") (pin "E") (pinfunction "E_E") (pintype "passive"))
      (node (ref "X1") (pin "4") (pinfunction "VCC_4") (pintype "power_in"))
    )
    (net (code "80") (name "unconnected-(IC3-PB00_01-Pad11)") (class "Default")
      (node (ref "IC3") (pin "11") (pinfunction "PB00_01_11") (pintype "bidirectional"))
    )
    (net (code "81") (name "unconnected-(IC3-PB00_02-Pad12)") (class "Default")
      (node (ref "IC3") (pin "12") (pinfunction "PB00_02_12") (pintype "bidirectional"))
    )
    (net (code "82") (name "unconnected-(IC3-PB00_04-Pad13)") (class "Default")
      (node (ref "IC3") (pin "13") (pinfunction "PB00_04_13") (pintype "bidirectional"))
    )
    (net (code "83") (name "unconnected-(IC3-PB00_05-Pad14)") (class "Default")
      (node (ref "IC3") (pin "14") (pinfunction "PB00_05_14") (pintype "bidirectional"))
    )
    (net (code "84") (name "unconnected-(IC3-PB01_07{slash}GTS1-Pad3)") (class "Default")
      (node (ref "IC3") (pin "3") (pinfunction "PB01_07/GTS1_3") (pintype "bidirectional"))
    )
    (net (code "85") (name "unconnected-(IC3-PB03_05-Pad90)") (class "Default")
      (node (ref "IC3") (pin "90") (pinfunction "PB03_05_90") (pintype "bidirectional"))
    )
    (net (code "86") (name "unconnected-(IC3-PB03_07-Pad91)") (class "Default")
      (node (ref "IC3") (pin "91") (pinfunction "PB03_07_91") (pintype "bidirectional"))
    )
    (net (code "87") (name "unconnected-(IC3-PB03_08-Pad92)") (class "Default")
      (node (ref "IC3") (pin "92") (pinfunction "PB03_08_92") (pintype "bidirectional"))
    )
    (net (code "88") (name "unconnected-(IC3-PB03_13-Pad95)") (class "Default")
      (node (ref "IC3") (pin "95") (pinfunction "PB03_13_95") (pintype "bidirectional"))
    )
    (net (code "89") (name "unconnected-(IC3-PB03_16-Pad97)") (class "Default")
      (node (ref "IC3") (pin "97") (pinfunction "PB03_16_97") (pintype "bidirectional"))
    )
    (net (code "90") (name "unconnected-(IC3-PB04_07-Pad39)") (class "Default")
      (node (ref "IC3") (pin "39") (pinfunction "PB04_07_39") (pintype "bidirectional"))
    )
    (net (code "91") (name "unconnected-(IC3-PB04_08-Pad40)") (class "Default")
      (node (ref "IC3") (pin "40") (pinfunction "PB04_08_40") (pintype "bidirectional"))
    )
    (net (code "92") (name "unconnected-(IC3-PB04_14-Pad46)") (class "Default")
      (node (ref "IC3") (pin "46") (pinfunction "PB04_14_46") (pintype "bidirectional"))
    )
    (net (code "93") (name "unconnected-(IC3-PB05_01-Pad74)") (class "Default")
      (node (ref "IC3") (pin "74") (pinfunction "PB05_01_74") (pintype "bidirectional"))
    )
    (net (code "94") (name "unconnected-(IC3-PB06_05-Pad53)") (class "Default")
      (node (ref "IC3") (pin "53") (pinfunction "PB06_05_53") (pintype "bidirectional"))
    )
    (net (code "95") (name "unconnected-(IC3-PB06_14-Pad60)") (class "Default")
      (node (ref "IC3") (pin "60") (pinfunction "PB06_14_60") (pintype "bidirectional"))
    )
    (net (code "96") (name "unconnected-(IC3-PB06_16-Pad61)") (class "Default")
      (node (ref "IC3") (pin "61") (pinfunction "PB06_16_61") (pintype "bidirectional"))
    )
    (net (code "97") (name "unconnected-(IC3-PB07_01-Pad63)") (class "Default")
      (node (ref "IC3") (pin "63") (pinfunction "PB07_01_63") (pintype "bidirectional"))
    )
    (net (code "98") (name "unconnected-(IC3-PB07_10-Pad68)") (class "Default")
      (node (ref "IC3") (pin "68") (pinfunction "PB07_10_68") (pintype "bidirectional"))
    )
    (net (code "99") (name "unconnected-(IC3-PB07_13-Pad71)") (class "Default")
      (node (ref "IC3") (pin "71") (pinfunction "PB07_13_71") (pintype "bidirectional"))
    )
    (net (code "100") (name "unconnected-(IC3-PB07_14-Pad72)") (class "Default")
      (node (ref "IC3") (pin "72") (pinfunction "PB07_14_72") (pintype "bidirectional"))
    )
    (net (code "101") (name "unconnected-(IC3-PB07_16-Pad73)") (class "Default")
      (node (ref "IC3") (pin "73") (pinfunction "PB07_16_73") (pintype "bidirectional"))
    )
    (net (code "102") (name "unconnected-(JP1-CLOCK-Pad42)") (class "Default")
      (node (ref "JP1") (pin "42") (pinfunction "CLOCK_42") (pintype "output"))
    )
    (net (code "103") (name "unconnected-(JP1-RES-Pad5)") (class "Default")
      (node (ref "JP1") (pin "5") (pinfunction "RES_5") (pintype "no_connect"))
    )
    (net (code "104") (name "unconnected-(JP1-RES-Pad16)") (class "Default")
      (node (ref "JP1") (pin "16") (pinfunction "RES_16") (pintype "no_connect"))
    )
    (net (code "105") (name "unconnected-(JP1-SOUNDIN-Pad49)") (class "Default")
      (node (ref "JP1") (pin "49") (pinfunction "SOUNDIN_49") (pintype "passive"))
    )
    (net (code "106") (name "unconnected-(JP1-~{CS1}-Pad1)") (class "Default")
      (node (ref "JP1") (pin "1") (pinfunction "~{CS1}_1") (pintype "output"))
    )
    (net (code "107") (name "unconnected-(JP1-~{CS2}-Pad2)") (class "Default")
      (node (ref "JP1") (pin "2") (pinfunction "~{CS2}_2") (pintype "output"))
    )
    (net (code "108") (name "unconnected-(JP1-~{CS12}-Pad3)") (class "Default")
      (node (ref "JP1") (pin "3") (pinfunction "~{CS12}_3") (pintype "output"))
    )
    (net (code "109") (name "unconnected-(JP1-~{RFSH}-Pad6)") (class "Default")
      (node (ref "JP1") (pin "6") (pinfunction "~{RFSH}_6") (pintype "output"))
    )
    (net (code "110") (name "unconnected-(JT1-Pad6)") (class "Default")
      (node (ref "JT1") (pin "6") (pinfunction "6_6") (pintype "passive"))
    )
    (net (code "111") (name "unconnected-(JT1-Pad7)") (class "Default")
      (node (ref "JT1") (pin "7") (pinfunction "7_7") (pintype "passive"))
    )
    (net (code "112") (name "unconnected-(JT1-Pad8)") (class "Default")
      (node (ref "JT1") (pin "8") (pinfunction "8_8") (pintype "passive"))
    )
    (net (code "113") (name "unconnected-(S1-S-Pad3)") (class "Default")
      (node (ref "S1") (pin "3") (pinfunction "S_3") (pintype "passive"))
    )
    (net (code "114") (name "unconnected-(S2-S-Pad3)") (class "Default")
      (node (ref "S2") (pin "3") (pinfunction "S_3") (pintype "passive"))
    )
    (net (code "115") (name "unconnected-(SD1-DAT1-Pad8)") (class "Default")
      (node (ref "SD1") (pin "8") (pinfunction "DAT1_8") (pintype "bidirectional"))
    )
    (net (code "116") (name "unconnected-(SD1-DAT2-Pad9)") (class "Default")
      (node (ref "SD1") (pin "9") (pinfunction "DAT2_9") (pintype "bidirectional"))
    )
    (net (code "117") (name "unconnected-(SD2-DAT1-Pad8)") (class "Default")
      (node (ref "SD2") (pin "8") (pinfunction "DAT1_8") (pintype "bidirectional"))
    )
    (net (code "118") (name "unconnected-(SD2-DAT2-Pad9)") (class "Default")
      (node (ref "SD2") (pin "9") (pinfunction "DAT2_9") (pintype "bidirectional"))
    )
    (net (code "119") (name "unconnected-(X1-E{slash}D-Pad1)") (class "Default")
      (node (ref "X1") (pin "1") (pinfunction "E/D_1") (pintype "input"))
    )
  )
)
